# SuperClock_Core_PWR.net
KiCad netlist of a schematic drawn in Altium Designer
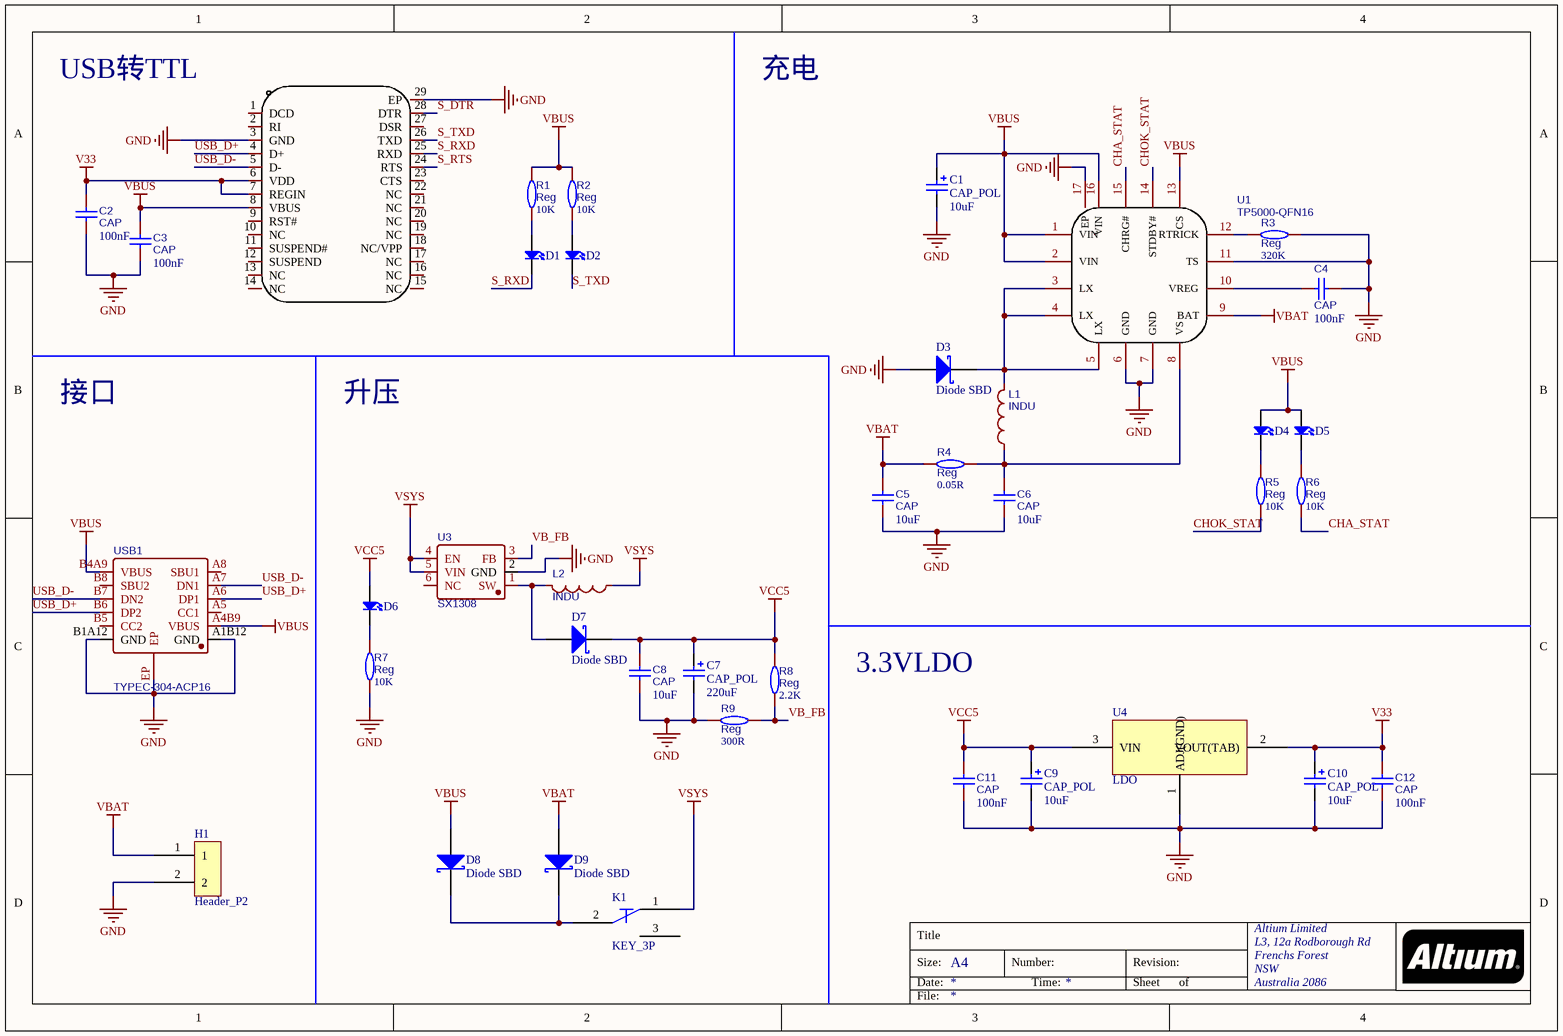
[diagram p0: SuperClock_Core_PWR.SchDoc]

(export (version "E")
  (design (tool "Eeschema 10.0.6"))
  (components
    (comp (ref "C1")
      (value "CAP_POL")
      (footprint "CP1210")
      (description "极性电容")
      (fields (field (name "ALTIUM_VALUE") "10uF"))
      (libsource (lib "Levent_lib") (part "CAP_POL"))
    )
    (comp (ref "C2")
      (value "CAP")
      (footprint "C0603")
      (description "Cap")
      (fields
        (field (name "BOM_SUPPLIER PART") "C302008")
        (field (name "BOM_MANUFACTURER PART") "0603B103K101CT")
        (field (name "ALTIUM_VALUE") "100nF")
        (field (name "CONTRIBUTOR") "LCSC")
      )
      (libsource (lib "Levent_lib") (part "CAP"))
    )
    (comp (ref "C3")
      (value "CAP")
      (footprint "C0603")
      (description "Cap")
      (fields
        (field (name "BOM_SUPPLIER PART") "C302008")
        (field (name "BOM_MANUFACTURER PART") "0603B103K101CT")
        (field (name "ALTIUM_VALUE") "100nF")
        (field (name "CONTRIBUTOR") "LCSC")
      )
      (libsource (lib "Levent_lib") (part "CAP"))
    )
    (comp (ref "C4")
      (value "CAP")
      (footprint "C0603")
      (description "Cap")
      (fields
        (field (name "BOM_SUPPLIER PART") "C302008")
        (field (name "BOM_MANUFACTURER PART") "0603B103K101CT")
        (field (name "ALTIUM_VALUE") "100nF")
        (field (name "CONTRIBUTOR") "LCSC")
      )
      (libsource (lib "Levent_lib") (part "CAP"))
    )
    (comp (ref "C5")
      (value "CAP")
      (footprint "C0603")
      (description "Cap")
      (fields
        (field (name "BOM_SUPPLIER PART") "C302008")
        (field (name "BOM_MANUFACTURER PART") "0603B103K101CT")
        (field (name "ALTIUM_VALUE") "10uF")
        (field (name "CONTRIBUTOR") "LCSC")
      )
      (libsource (lib "Levent_lib") (part "CAP"))
    )
    (comp (ref "C6")
      (value "CAP")
      (footprint "C0603")
      (description "Cap")
      (fields
        (field (name "BOM_SUPPLIER PART") "C302008")
        (field (name "BOM_MANUFACTURER PART") "0603B103K101CT")
        (field (name "ALTIUM_VALUE") "10uF")
        (field (name "CONTRIBUTOR") "LCSC")
      )
      (libsource (lib "Levent_lib") (part "CAP"))
    )
    (comp (ref "C7")
      (value "CAP_POL")
      (footprint "CAP_SMD_6.3mm")
      (description "极性电容")
      (fields (field (name "ALTIUM_VALUE") "220uF"))
      (libsource (lib "Levent_lib") (part "CAP_POL"))
    )
    (comp (ref "C8")
      (value "CAP")
      (footprint "C0603")
      (description "Cap")
      (fields
        (field (name "BOM_SUPPLIER PART") "C302008")
        (field (name "BOM_MANUFACTURER PART") "0603B103K101CT")
        (field (name "ALTIUM_VALUE") "10uF")
        (field (name "CONTRIBUTOR") "LCSC")
      )
      (libsource (lib "Levent_lib") (part "CAP"))
    )
    (comp (ref "C9")
      (value "CAP_POL")
      (footprint "CP1210")
      (description "极性电容")
      (fields (field (name "ALTIUM_VALUE") "10uF"))
      (libsource (lib "Levent_lib") (part "CAP_POL"))
    )
    (comp (ref "C10")
      (value "CAP_POL")
      (footprint "CP1210")
      (description "极性电容")
      (fields (field (name "ALTIUM_VALUE") "10uF"))
      (libsource (lib "Levent_lib") (part "CAP_POL"))
    )
    (comp (ref "C11")
      (value "CAP")
      (footprint "C0603")
      (description "Cap")
      (fields
        (field (name "BOM_SUPPLIER PART") "C302008")
        (field (name "BOM_MANUFACTURER PART") "0603B103K101CT")
        (field (name "ALTIUM_VALUE") "100nF")
        (field (name "CONTRIBUTOR") "LCSC")
      )
      (libsource (lib "Levent_lib") (part "CAP"))
    )
    (comp (ref "C12")
      (value "CAP")
      (footprint "C0603")
      (description "Cap")
      (fields
        (field (name "BOM_SUPPLIER PART") "C302008")
        (field (name "BOM_MANUFACTURER PART") "0603B103K101CT")
        (field (name "ALTIUM_VALUE") "100nF")
        (field (name "CONTRIBUTOR") "LCSC")
      )
      (libsource (lib "Levent_lib") (part "CAP"))
    )
    (comp (ref "D1")
      (value "LED")
      (footprint "LED0603")
      (fields (field (name "PUBLISHER") "Altium Limited"))
      (libsource (lib "Levent_lib") (part "LED0"))
    )
    (comp (ref "D2")
      (value "LED")
      (footprint "LED0603")
      (fields (field (name "PUBLISHER") "Altium Limited"))
      (libsource (lib "Levent_lib") (part "LED0"))
    )
    (comp (ref "D3")
      (value "Diode SBD")
      (footprint "SMA_L4.3")
      (description "Schottky Rectifier")
      (fields (field (name "PUBLISHER") "Altium Limited"))
      (libsource (lib "Levent_lib") (part "Diode SBD"))
    )
    (comp (ref "D4")
      (value "LED")
      (footprint "LED0603")
      (fields (field (name "PUBLISHER") "Altium Limited"))
      (libsource (lib "Levent_lib") (part "LED0"))
    )
    (comp (ref "D5")
      (value "LED")
      (footprint "LED0603")
      (fields (field (name "PUBLISHER") "Altium Limited"))
      (libsource (lib "Levent_lib") (part "LED0"))
    )
    (comp (ref "D6")
      (value "LED")
      (footprint "LED0603")
      (fields (field (name "PUBLISHER") "Altium Limited"))
      (libsource (lib "Levent_lib") (part "LED0"))
    )
    (comp (ref "D7")
      (value "Diode SBD")
      (footprint "SMA_L4.3")
      (description "Schottky Rectifier")
      (fields (field (name "PUBLISHER") "Altium Limited"))
      (libsource (lib "Levent_lib") (part "Diode SBD"))
    )
    (comp (ref "D8")
      (value "Diode SBD")
      (footprint "SMA_L4.3")
      (description "Schottky Rectifier")
      (fields (field (name "PUBLISHER") "Altium Limited"))
      (libsource (lib "Levent_lib") (part "Diode SBD"))
    )
    (comp (ref "D9")
      (value "Diode SBD")
      (footprint "SMA_L4.3")
      (description "Schottky Rectifier")
      (fields (field (name "PUBLISHER") "Altium Limited"))
      (libsource (lib "Levent_lib") (part "Diode SBD"))
    )
    (comp (ref "H1")
      (value "Header_P2")
      (footprint "PH_2Pin")
      (description "2Pin排针")
      (libsource (lib "Levent_lib") (part "Header_P2"))
    )
    (comp (ref "K1")
      (value "KEY_3P")
      (footprint "SWITCH_3P_2")
      (description "3Pin按键")
      (libsource (lib "Levent_lib") (part "KEY_3P"))
    )
    (comp (ref "L1")
      (value "INDU")
      (footprint "SMD_L7.1")
      (description "电感")
      (fields
        (field (name "BOM_SUPPLIER PART") "C182182")
        (field (name "BOM_MANUFACTURER PART") "SLO0630H150MTT")
        (field (name "CONTRIBUTOR") "LCSC")
      )
      (libsource (lib "Levent_lib") (part "IND"))
    )
    (comp (ref "L2")
      (value "INDU")
      (footprint "SMD_L7.1")
      (description "电感")
      (fields
        (field (name "BOM_SUPPLIER PART") "C182182")
        (field (name "BOM_MANUFACTURER PART") "SLO0630H150MTT")
        (field (name "CONTRIBUTOR") "LCSC")
      )
      (libsource (lib "Levent_lib") (part "IND"))
    )
    (comp (ref "R1")
      (value "Reg")
      (footprint "R0603")
      (description "电阻")
      (fields
        (field (name "BOM_SUPPLIER PART") "C465721")
        (field (name "BOM_MANUFACTURER PART") "AR03BTCX1002A")
        (field (name "ALTIUM_VALUE") "10K")
        (field (name "CONTRIBUTOR") "LCSC")
      )
      (libsource (lib "Levent_lib") (part "Res"))
    )
    (comp (ref "R2")
      (value "Reg")
      (footprint "R0603")
      (description "电阻")
      (fields
        (field (name "BOM_SUPPLIER PART") "C465721")
        (field (name "BOM_MANUFACTURER PART") "AR03BTCX1002A")
        (field (name "ALTIUM_VALUE") "10K")
        (field (name "CONTRIBUTOR") "LCSC")
      )
      (libsource (lib "Levent_lib") (part "Res"))
    )
    (comp (ref "R3")
      (value "Reg")
      (footprint "R0603")
      (description "电阻")
      (fields
        (field (name "BOM_SUPPLIER PART") "C465721")
        (field (name "BOM_MANUFACTURER PART") "AR03BTCX1002A")
        (field (name "ALTIUM_VALUE") "320K")
        (field (name "CONTRIBUTOR") "LCSC")
      )
      (libsource (lib "Levent_lib") (part "Res"))
    )
    (comp (ref "R4")
      (value "Reg")
      (footprint "R1206")
      (description "电阻")
      (fields
        (field (name "BOM_SUPPLIER PART") "C465721")
        (field (name "BOM_MANUFACTURER PART") "AR03BTCX1002A")
        (field (name "ALTIUM_VALUE") "0.05R")
        (field (name "CONTRIBUTOR") "LCSC")
      )
      (libsource (lib "Levent_lib") (part "Res"))
    )
    (comp (ref "R5")
      (value "Reg")
      (footprint "R0603")
      (description "电阻")
      (fields
        (field (name "BOM_SUPPLIER PART") "C465721")
        (field (name "BOM_MANUFACTURER PART") "AR03BTCX1002A")
        (field (name "ALTIUM_VALUE") "10K")
        (field (name "CONTRIBUTOR") "LCSC")
      )
      (libsource (lib "Levent_lib") (part "Res"))
    )
    (comp (ref "R6")
      (value "Reg")
      (footprint "R0603")
      (description "电阻")
      (fields
        (field (name "BOM_SUPPLIER PART") "C465721")
        (field (name "BOM_MANUFACTURER PART") "AR03BTCX1002A")
        (field (name "ALTIUM_VALUE") "10K")
        (field (name "CONTRIBUTOR") "LCSC")
      )
      (libsource (lib "Levent_lib") (part "Res"))
    )
    (comp (ref "R7")
      (value "Reg")
      (footprint "R0603")
      (description "电阻")
      (fields
        (field (name "BOM_SUPPLIER PART") "C465721")
        (field (name "BOM_MANUFACTURER PART") "AR03BTCX1002A")
        (field (name "ALTIUM_VALUE") "10K")
        (field (name "CONTRIBUTOR") "LCSC")
      )
      (libsource (lib "Levent_lib") (part "Res"))
    )
    (comp (ref "R8")
      (value "Reg")
      (footprint "R0603")
      (description "电阻")
      (fields
        (field (name "BOM_SUPPLIER PART") "C465721")
        (field (name "BOM_MANUFACTURER PART") "AR03BTCX1002A")
        (field (name "ALTIUM_VALUE") "2.2K")
        (field (name "CONTRIBUTOR") "LCSC")
      )
      (libsource (lib "Levent_lib") (part "Res"))
    )
    (comp (ref "R9")
      (value "Reg")
      (footprint "R0603")
      (description "电阻")
      (fields
        (field (name "BOM_SUPPLIER PART") "C465721")
        (field (name "BOM_MANUFACTURER PART") "AR03BTCX1002A")
        (field (name "ALTIUM_VALUE") "300R")
        (field (name "CONTRIBUTOR") "LCSC")
      )
      (libsource (lib "Levent_lib") (part "Res"))
    )
    (comp (ref "U1")
      (value "TP5000-QFN16")
      (footprint "QFN-16_L4.0-W4.0-P0.65-BL-EP2.2")
      (fields (field (name "BOM_SUPPLIER PART") "C51699"))
      (libsource (lib "Levent_lib") (part "TP5000-QFN16"))
    )
    (comp (ref "U2")
      (value "CP2102-GM")
      (footprint "QFN-28")
      (description "CP2102USB转串口")
      (fields (field (name "MANUFACTURER") "SILICON LABS(芯科)"))
      (libsource (lib "Levent_lib") (part "CP2102-GM"))
    )
    (comp (ref "U3")
      (value "SX1308")
      (footprint "SOT-23-6")
      (description "升压PWM")
      (fields (field (name "BOM_SUPPLIER PART") "C78162"))
      (libsource (lib "Levent_lib") (part "SX1308"))
    )
    (comp (ref "U4") (value "LDO") (footprint "SOT-223") (libsource (lib "Levent_lib") (part "AMS1117")))
    (comp (ref "USB1")
      (value "TYPEC-304-ACP16")
      (footprint "USB-C-SMD_TYPE-C-16P")
      (description "全引脚USB TYPEC母座")
      (fields (field (name "BOM_SUPPLIER PART") "C2982555") (field (name "CONTRIBUTOR") "LCSC"))
      (libsource (lib "Levent_lib") (part "USB_TYPEC_12P"))
    )
  )
  (nets
    (net (code "1") (name "/CHA_STAT") (class "Default")
      (node (ref "R6") (pin "1") (pinfunction "1_1") (pintype "passive"))
      (node (ref "U1") (pin "15") (pinfunction "CHRG#_15") (pintype "passive"))
    )
    (net (code "2") (name "/CHOK_STAT") (class "Default")
      (node (ref "R5") (pin "1") (pinfunction "1_1") (pintype "passive"))
      (node (ref "U1") (pin "14") (pinfunction "STDBY#_14") (pintype "passive"))
    )
    (net (code "3") (name "/S_DTR") (class "Default")
      (node (ref "U2") (pin "28") (pinfunction "DTR_28") (pintype "passive"))
    )
    (net (code "4") (name "/S_RTS") (class "Default")
      (node (ref "U2") (pin "24") (pinfunction "RTS_24") (pintype "passive"))
    )
    (net (code "5") (name "/S_RXD") (class "Default")
      (node (ref "D1") (pin "1") (pinfunction "K_1") (pintype "passive"))
      (node (ref "U2") (pin "25") (pinfunction "RXD_25") (pintype "passive"))
    )
    (net (code "6") (name "/S_TXD") (class "Default")
      (node (ref "D2") (pin "1") (pinfunction "K_1") (pintype "passive"))
      (node (ref "U2") (pin "26") (pinfunction "TXD_26") (pintype "passive"))
    )
    (net (code "7") (name "/USB_D+") (class "Default")
      (node (ref "U2") (pin "4") (pinfunction "D+_4") (pintype "passive"))
      (node (ref "USB1") (pin "A6") (pinfunction "DP1_A6") (pintype "passive"))
      (node (ref "USB1") (pin "B6") (pinfunction "DP2_B6") (pintype "passive"))
    )
    (net (code "8") (name "/USB_D-") (class "Default")
      (node (ref "U2") (pin "5") (pinfunction "D-_5") (pintype "passive"))
      (node (ref "USB1") (pin "A7") (pinfunction "DN1_A7") (pintype "passive"))
      (node (ref "USB1") (pin "B7") (pinfunction "DN2_B7") (pintype "passive"))
    )
    (net (code "9") (name "/VB_FB") (class "Default")
      (node (ref "R8") (pin "1") (pinfunction "1_1") (pintype "passive"))
      (node (ref "R9") (pin "1") (pinfunction "1_1") (pintype "passive"))
      (node (ref "U3") (pin "3") (pinfunction "FB_3") (pintype "passive"))
    )
    (net (code "10") (name "GND") (class "Default")
      (node (ref "C1") (pin "2") (pinfunction "2_2") (pintype "passive"))
      (node (ref "C10") (pin "2") (pinfunction "2_2") (pintype "passive"))
      (node (ref "C11") (pin "2") (pinfunction "2_2") (pintype "passive"))
      (node (ref "C12") (pin "2") (pinfunction "2_2") (pintype "passive"))
      (node (ref "C2") (pin "2") (pinfunction "2_2") (pintype "passive"))
      (node (ref "C3") (pin "2") (pinfunction "2_2") (pintype "passive"))
      (node (ref "C4") (pin "2") (pinfunction "2_2") (pintype "passive"))
      (node (ref "C5") (pin "2") (pinfunction "2_2") (pintype "passive"))
      (node (ref "C6") (pin "2") (pinfunction "2_2") (pintype "passive"))
      (node (ref "C7") (pin "2") (pinfunction "2_2") (pintype "passive"))
      (node (ref "C8") (pin "2") (pinfunction "2_2") (pintype "passive"))
      (node (ref "C9") (pin "2") (pinfunction "2_2") (pintype "passive"))
      (node (ref "D3") (pin "2") (pinfunction "A_2") (pintype "passive"))
      (node (ref "H1") (pin "2") (pinfunction "2_2") (pintype "passive"))
      (node (ref "R3") (pin "2") (pinfunction "2_2") (pintype "passive"))
      (node (ref "R7") (pin "1") (pinfunction "1_1") (pintype "passive"))
      (node (ref "R9") (pin "2") (pinfunction "2_2") (pintype "passive"))
      (node (ref "U1") (pin "11") (pinfunction "TS_11") (pintype "passive"))
      (node (ref "U1") (pin "17") (pinfunction "EP_17") (pintype "passive"))
      (node (ref "U1") (pin "6") (pinfunction "GND_6") (pintype "passive"))
      (node (ref "U1") (pin "7") (pinfunction "GND_7") (pintype "passive"))
      (node (ref "U2") (pin "29") (pinfunction "EP_29") (pintype "passive"))
      (node (ref "U2") (pin "3") (pinfunction "GND_3") (pintype "passive"))
      (node (ref "U3") (pin "2") (pinfunction "GND_2") (pintype "passive"))
      (node (ref "U4") (pin "1") (pinfunction "ADJ(GND)_1") (pintype "passive"))
      (node (ref "USB1") (pin "A1B12") (pinfunction "GND_A1B12") (pintype "passive"))
      (node (ref "USB1") (pin "B1A12") (pinfunction "GND_B1A12") (pintype "passive"))
      (node (ref "USB1") (pin "EP") (pinfunction "EP_EP") (pintype "passive"))
    )
    (net (code "11") (name "Net-(D1-A)") (class "Default")
      (node (ref "D1") (pin "2") (pinfunction "A_2") (pintype "passive"))
      (node (ref "R1") (pin "1") (pinfunction "1_1") (pintype "passive"))
    )
    (net (code "12") (name "Net-(D2-A)") (class "Default")
      (node (ref "D2") (pin "2") (pinfunction "A_2") (pintype "passive"))
      (node (ref "R2") (pin "1") (pinfunction "1_1") (pintype "passive"))
    )
    (net (code "13") (name "Net-(D3-K)") (class "Default")
      (node (ref "D3") (pin "1") (pinfunction "K_1") (pintype "passive"))
      (node (ref "L1") (pin "2") (pinfunction "2_2") (pintype "passive"))
      (node (ref "U1") (pin "3") (pinfunction "LX_3") (pintype "passive"))
      (node (ref "U1") (pin "4") (pinfunction "LX_4") (pintype "passive"))
      (node (ref "U1") (pin "5") (pinfunction "LX_5") (pintype "passive"))
    )
    (net (code "14") (name "Net-(D4-K)") (class "Default")
      (node (ref "D4") (pin "1") (pinfunction "K_1") (pintype "passive"))
      (node (ref "R5") (pin "2") (pinfunction "2_2") (pintype "passive"))
    )
    (net (code "15") (name "Net-(D5-K)") (class "Default")
      (node (ref "D5") (pin "1") (pinfunction "K_1") (pintype "passive"))
      (node (ref "R6") (pin "2") (pinfunction "2_2") (pintype "passive"))
    )
    (net (code "16") (name "Net-(D6-K)") (class "Default")
      (node (ref "D6") (pin "1") (pinfunction "K_1") (pintype "passive"))
      (node (ref "R7") (pin "2") (pinfunction "2_2") (pintype "passive"))
    )
    (net (code "17") (name "Net-(D7-A)") (class "Default")
      (node (ref "D7") (pin "2") (pinfunction "A_2") (pintype "passive"))
      (node (ref "L2") (pin "2") (pinfunction "2_2") (pintype "passive"))
      (node (ref "U3") (pin "1") (pinfunction "SW_1") (pintype "passive"))
    )
    (net (code "18") (name "Net-(D8-K)") (class "Default")
      (node (ref "D8") (pin "1") (pinfunction "K_1") (pintype "passive"))
      (node (ref "D9") (pin "1") (pinfunction "K_1") (pintype "passive"))
      (node (ref "K1") (pin "2") (pinfunction "2_2") (pintype "passive"))
    )
    (net (code "19") (name "Net-(U1-RTRICK)") (class "Default")
      (node (ref "R3") (pin "1") (pinfunction "1_1") (pintype "passive"))
      (node (ref "U1") (pin "12") (pinfunction "RTRICK_12") (pintype "passive"))
    )
    (net (code "20") (name "Net-(U1-VREG)") (class "Default")
      (node (ref "C4") (pin "1") (pinfunction "1_1") (pintype "passive"))
      (node (ref "U1") (pin "10") (pinfunction "VREG_10") (pintype "passive"))
    )
    (net (code "21") (name "Net-(U1-VS)") (class "Default")
      (node (ref "C6") (pin "1") (pinfunction "1_1") (pintype "passive"))
      (node (ref "L1") (pin "1") (pinfunction "1_1") (pintype "passive"))
      (node (ref "R4") (pin "2") (pinfunction "2_2") (pintype "passive"))
      (node (ref "U1") (pin "8") (pinfunction "VS_8") (pintype "passive"))
    )
    (net (code "22") (name "V33") (class "Default")
      (node (ref "C10") (pin "1") (pinfunction "1_1") (pintype "passive"))
      (node (ref "C12") (pin "1") (pinfunction "1_1") (pintype "passive"))
      (node (ref "C2") (pin "1") (pinfunction "1_1") (pintype "passive"))
      (node (ref "U2") (pin "6") (pinfunction "VDD_6") (pintype "passive"))
      (node (ref "U2") (pin "7") (pinfunction "REGIN_7") (pintype "passive"))
      (node (ref "U4") (pin "2") (pinfunction "VOUT(TAB)_2") (pintype "passive"))
    )
    (net (code "23") (name "VBAT") (class "Default")
      (node (ref "C5") (pin "1") (pinfunction "1_1") (pintype "passive"))
      (node (ref "D9") (pin "2") (pinfunction "A_2") (pintype "passive"))
      (node (ref "H1") (pin "1") (pinfunction "1_1") (pintype "passive"))
      (node (ref "R4") (pin "1") (pinfunction "1_1") (pintype "passive"))
      (node (ref "U1") (pin "9") (pinfunction "BAT_9") (pintype "passive"))
    )
    (net (code "24") (name "VBUS") (class "Default")
      (node (ref "C1") (pin "1") (pinfunction "1_1") (pintype "passive"))
      (node (ref "C3") (pin "1") (pinfunction "1_1") (pintype "passive"))
      (node (ref "D4") (pin "2") (pinfunction "A_2") (pintype "passive"))
      (node (ref "D5") (pin "2") (pinfunction "A_2") (pintype "passive"))
      (node (ref "D8") (pin "2") (pinfunction "A_2") (pintype "passive"))
      (node (ref "R1") (pin "2") (pinfunction "2_2") (pintype "passive"))
      (node (ref "R2") (pin "2") (pinfunction "2_2") (pintype "passive"))
      (node (ref "U1") (pin "1") (pinfunction "VIN_1") (pintype "passive"))
      (node (ref "U1") (pin "13") (pinfunction "CS_13") (pintype "passive"))
      (node (ref "U1") (pin "16") (pinfunction "VIN_16") (pintype "passive"))
      (node (ref "U1") (pin "2") (pinfunction "VIN_2") (pintype "passive"))
      (node (ref "U2") (pin "8") (pinfunction "VBUS_8") (pintype "passive"))
      (node (ref "USB1") (pin "A4B9") (pinfunction "VBUS_A4B9") (pintype "passive"))
      (node (ref "USB1") (pin "B4A9") (pinfunction "VBUS_B4A9") (pintype "passive"))
    )
    (net (code "25") (name "VCC5") (class "Default")
      (node (ref "C11") (pin "1") (pinfunction "1_1") (pintype "passive"))
      (node (ref "C7") (pin "1") (pinfunction "1_1") (pintype "passive"))
      (node (ref "C8") (pin "1") (pinfunction "1_1") (pintype "passive"))
      (node (ref "C9") (pin "1") (pinfunction "1_1") (pintype "passive"))
      (node (ref "D6") (pin "2") (pinfunction "A_2") (pintype "passive"))
      (node (ref "D7") (pin "1") (pinfunction "K_1") (pintype "passive"))
      (node (ref "R8") (pin "2") (pinfunction "2_2") (pintype "passive"))
      (node (ref "U4") (pin "3") (pinfunction "VIN_3") (pintype "passive"))
    )
    (net (code "26") (name "VSYS") (class "Default")
      (node (ref "K1") (pin "1") (pinfunction "1_1") (pintype "passive"))
      (node (ref "L2") (pin "1") (pinfunction "1_1") (pintype "passive"))
      (node (ref "U3") (pin "4") (pinfunction "EN_4") (pintype "passive"))
      (node (ref "U3") (pin "5") (pinfunction "VIN_5") (pintype "passive"))
    )
    (net (code "27") (name "unconnected-(K1-Pad3)") (class "Default")
      (node (ref "K1") (pin "3") (pinfunction "3_3") (pintype "passive"))
    )
    (net (code "28") (name "unconnected-(U2-CTS-Pad23)") (class "Default")
      (node (ref "U2") (pin "23") (pinfunction "CTS_23") (pintype "passive"))
    )
    (net (code "29") (name "unconnected-(U2-DCD-Pad1)") (class "Default")
      (node (ref "U2") (pin "1") (pinfunction "DCD_1") (pintype "passive"))
    )
    (net (code "30") (name "unconnected-(U2-DSR-Pad27)") (class "Default")
      (node (ref "U2") (pin "27") (pinfunction "DSR_27") (pintype "passive"))
    )
    (net (code "31") (name "unconnected-(U2-NC-Pad10)") (class "Default")
      (node (ref "U2") (pin "10") (pinfunction "NC_10") (pintype "passive"))
    )
    (net (code "32") (name "unconnected-(U2-NC-Pad13)") (class "Default")
      (node (ref "U2") (pin "13") (pinfunction "NC_13") (pintype "passive"))
    )
    (net (code "33") (name "unconnected-(U2-NC-Pad14)") (class "Default")
      (node (ref "U2") (pin "14") (pinfunction "NC_14") (pintype "passive"))
    )
    (net (code "34") (name "unconnected-(U2-NC-Pad15)") (class "Default")
      (node (ref "U2") (pin "15") (pinfunction "NC_15") (pintype "passive"))
    )
    (net (code "35") (name "unconnected-(U2-NC-Pad16)") (class "Default")
      (node (ref "U2") (pin "16") (pinfunction "NC_16") (pintype "passive"))
    )
    (net (code "36") (name "unconnected-(U2-NC-Pad17)") (class "Default")
      (node (ref "U2") (pin "17") (pinfunction "NC_17") (pintype "passive"))
    )
    (net (code "37") (name "unconnected-(U2-NC-Pad19)") (class "Default")
      (node (ref "U2") (pin "19") (pinfunction "NC_19") (pintype "passive"))
    )
    (net (code "38") (name "unconnected-(U2-NC-Pad20)") (class "Default")
      (node (ref "U2") (pin "20") (pinfunction "NC_20") (pintype "passive"))
    )
    (net (code "39") (name "unconnected-(U2-NC-Pad21)") (class "Default")
      (node (ref "U2") (pin "21") (pinfunction "NC_21") (pintype "passive"))
    )
    (net (code "40") (name "unconnected-(U2-NC-Pad22)") (class "Default")
      (node (ref "U2") (pin "22") (pinfunction "NC_22") (pintype "passive"))
    )
    (net (code "41") (name "unconnected-(U2-NC{slash}VPP-Pad18)") (class "Default")
      (node (ref "U2") (pin "18") (pinfunction "NC/VPP_18") (pintype "passive"))
    )
    (net (code "42") (name "unconnected-(U2-RI-Pad2)") (class "Default")
      (node (ref "U2") (pin "2") (pinfunction "RI_2") (pintype "passive"))
    )
    (net (code "43") (name "unconnected-(U2-RST#-Pad9)") (class "Default")
      (node (ref "U2") (pin "9") (pinfunction "RST#_9") (pintype "passive"))
    )
    (net (code "44") (name "unconnected-(U2-SUSPEND#-Pad11)") (class "Default")
      (node (ref "U2") (pin "11") (pinfunction "SUSPEND#_11") (pintype "passive"))
    )
    (net (code "45") (name "unconnected-(U2-SUSPEND-Pad12)") (class "Default")
      (node (ref "U2") (pin "12") (pinfunction "SUSPEND_12") (pintype "passive"))
    )
    (net (code "46") (name "unconnected-(U3-NC-Pad6)") (class "Default")
      (node (ref "U3") (pin "6") (pinfunction "NC_6") (pintype "passive"))
    )
    (net (code "47") (name "unconnected-(USB1-CC1-PadA5)") (class "Default")
      (node (ref "USB1") (pin "A5") (pinfunction "CC1_A5") (pintype "passive"))
    )
    (net (code "48") (name "unconnected-(USB1-CC2-PadB5)") (class "Default")
      (node (ref "USB1") (pin "B5") (pinfunction "CC2_B5") (pintype "passive"))
    )
    (net (code "49") (name "unconnected-(USB1-SBU1-PadA8)") (class "Default")
      (node (ref "USB1") (pin "A8") (pinfunction "SBU1_A8") (pintype "passive"))
    )
    (net (code "50") (name "unconnected-(USB1-SBU2-PadB8)") (class "Default")
      (node (ref "USB1") (pin "B8") (pinfunction "SBU2_B8") (pintype "passive"))
    )
  )
)
